# Copy_of_-5V_Buck_and_Power_Jack.net
KiCad netlist of a schematic drawn in Altium Designer
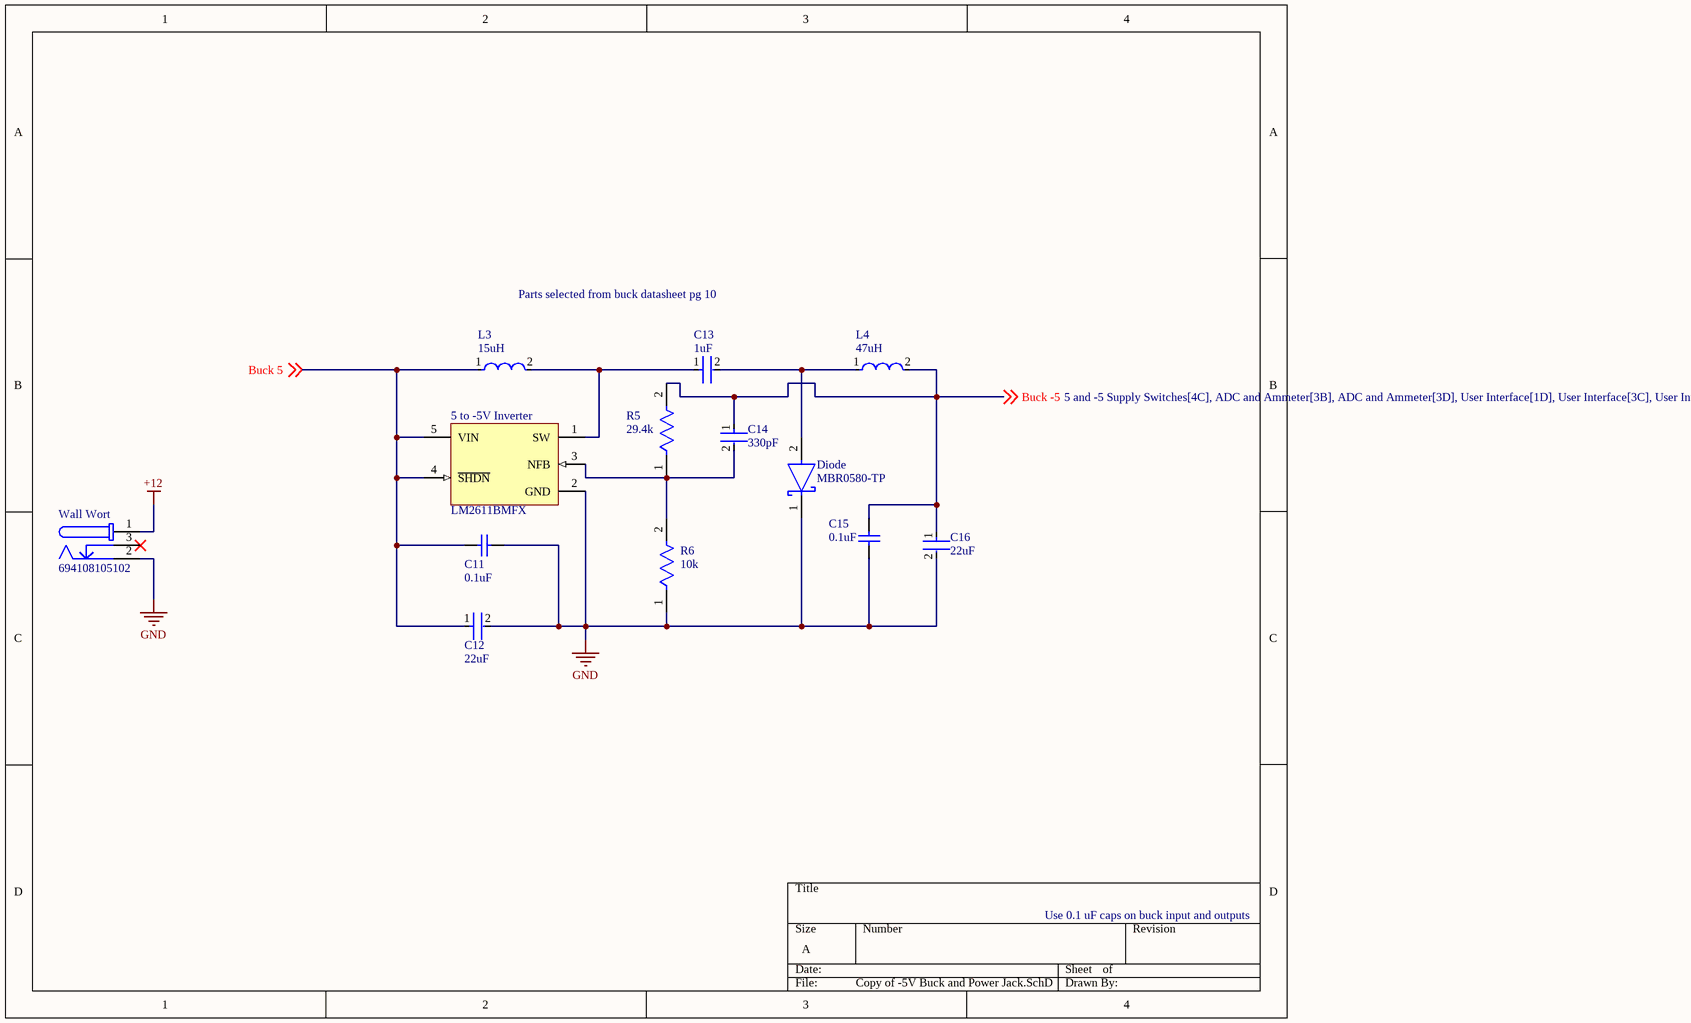
[diagram p0: Copy of -5V Buck and Power Jack.SchDoc]

(export (version "E")
  (design (tool "Eeschema 10.0.6"))
  (components
    (comp (ref "5 to -5V Inverter")
      (value "LM2611BMFX")
      (footprint "MF05A_N")
      (description "1.4MHz Cuk Converter, 5-pin SOT-23")
      (fields (field (name "MANUFACTURER") "National Semiconductor"))
      (libsource (lib "Altium Content Vault") (part "PM-DCDC-LM2611"))
    )
    (comp (ref "C11")
      (value "0.1uF")
      (footprint "CAPC2013X94X50LL20T25")
      (fields
        (field (name "PART NUMBER") "08055C104JAT4A")
        (field (name "MANUFACTURER") "AVX Interconnect / Elco")
      )
      (libsource (lib "Altium Content Vault") (part "CAP"))
    )
    (comp (ref "C12")
      (value "22uF")
      (footprint "FP-CL21-IPC_C")
      (description "CL21 Series 0805 22uF 25V ±20% Tolerance X5R Multilayer Ceramic Chip Capacitor")
      (libsource (lib "Altium Content Vault") (part "b4654b650e69147ec39a6b967a45e02"))
    )
    (comp (ref "C13")
      (value "1uF")
      (footprint "FP-CL10-IPC_B")
      (description "Cap Ceramic 1uF 25V X5R ±10% Pad SMD 0603 +85°C T/R")
      (fields (field (name "TOLERANCE") "10%"))
      (libsource (lib "Altium Content Vault") (part "b4654b650e69147ec39a6b967a45e02"))
    )
    (comp (ref "C14")
      (value "330pF")
      (footprint "FP-C0603C-CF-MFG")
      (description "C0603 330 pF X8R 30ppm/°C 20.00% 50 V")
      (fields (field (name "TOLERANCE") "0.2") (field (name "MANUFACTURER") "KEMET"))
      (libsource (lib "Altium Content Vault") (part "b4654b650e69147ec39a6b967a45e02"))
    )
    (comp (ref "C15")
      (value "0.1uF")
      (footprint "CAPC2013X94X50LL20T25")
      (fields
        (field (name "PART NUMBER") "08055C104JAT4A")
        (field (name "MANUFACTURER") "AVX Interconnect / Elco")
      )
      (libsource (lib "Altium Content Vault") (part "CAP"))
    )
    (comp (ref "C16")
      (value "22uF")
      (footprint "FP-CL21-IPC_C")
      (description "CL21 Series 0805 22uF 25V ±20% Tolerance X5R Multilayer Ceramic Chip Capacitor")
      (libsource (lib "Altium Content Vault") (part "b4654b650e69147ec39a6b967a45e02"))
    )
    (comp (ref "Diode")
      (value "MBR0580-TP")
      (footprint "FP-SOD-123-IPC_C")
      (description "DIODE SCHOTTKY 80V 500MA SOD123")
      (libsource (lib "Altium Content Vault") (part "1d6ec82d83fb6aee721767c19dac4b9"))
    )
    (comp (ref "L3")
      (value "15uH")
      (footprint "FP-SRR1260-MFG")
      (description "FIXED IND 15UH 5A 27 MOHM SMD")
      (fields (field (name "TOLERANCE") "20%"))
      (libsource (lib "Altium Content Vault") (part "725321dda6339637d4d059423bc1c3c"))
    )
    (comp (ref "L4")
      (value "47uH")
      (footprint "FP-SRP1265A-MFG")
      (description "FIXED IND 47UH 6.5A 90 MOHM SMD")
      (fields (field (name "TOLERANCE") "20%"))
      (libsource (lib "Altium Content Vault") (part "725321dda6339637d4d059423bc1c3c"))
    )
    (comp (ref "R5")
      (value "29.4k")
      (footprint "FP-AC0603-MFG")
      (description "RES 29.4KΩ 1.00% 0.1W 0603")
      (fields (field (name "TOLERANCE") "1%"))
      (libsource (lib "Altium Content Vault") (part "1029c3af85768c4190bb7ad29bc67b5"))
    )
    (comp (ref "R6")
      (value "10k")
      (footprint "FP-RK73H1J-IPC_B")
      (description "10kΩ ±1% 0.1W Chip Resistor 0603 Thick Film AEC-Q200 Qualified")
      (fields (field (name "TOLERANCE") "1%"))
      (libsource (lib "Altium Content Vault") (part "1029c3af85768c4190bb7ad29bc67b5"))
    )
    (comp (ref "Wall Wort")
      (value "694108105102")
      (footprint "694108105102")
      (libsource (lib "Altium Content Vault") (part "DC Power Jack"))
    )
  )
  (nets
    (net (code "1") (name "+12") (class "Default")
      (node (ref "Wall Wort") (pin "1") (pinfunction "1_1") (pintype "passive"))
    )
    (net (code "2") (name "Buck -5") (class "Default")
      (node (ref "C14") (pin "1") (pinfunction "1_1") (pintype "passive"))
      (node (ref "C15") (pin "2") (pinfunction "2_2") (pintype "passive"))
      (node (ref "C16") (pin "1") (pinfunction "1_1") (pintype "passive"))
      (node (ref "L4") (pin "2") (pinfunction "2_2") (pintype "passive"))
      (node (ref "R5") (pin "2") (pinfunction "2_2") (pintype "passive"))
    )
    (net (code "3") (name "Buck 5") (class "Default")
      (node (ref "5 to -5V Inverter") (pin "4") (pinfunction "~{SHDN}_4") (pintype "input"))
      (node (ref "5 to -5V Inverter") (pin "5") (pinfunction "VIN_5") (pintype "power_in"))
      (node (ref "C11") (pin "1") (pinfunction "1_1") (pintype "passive"))
      (node (ref "C12") (pin "1") (pinfunction "1_1") (pintype "passive"))
      (node (ref "L3") (pin "1") (pinfunction "1_1") (pintype "passive"))
    )
    (net (code "4") (name "GND") (class "Default")
      (node (ref "5 to -5V Inverter") (pin "2") (pinfunction "GND_2") (pintype "power_in"))
      (node (ref "C11") (pin "2") (pinfunction "2_2") (pintype "passive"))
      (node (ref "C12") (pin "2") (pinfunction "2_2") (pintype "passive"))
      (node (ref "C15") (pin "1") (pinfunction "1_1") (pintype "passive"))
      (node (ref "C16") (pin "2") (pinfunction "2_2") (pintype "passive"))
      (node (ref "Diode") (pin "1") (pinfunction "C_1") (pintype "passive"))
      (node (ref "R6") (pin "1") (pinfunction "1_1") (pintype "passive"))
      (node (ref "Wall Wort") (pin "2") (pinfunction "2_2") (pintype "passive"))
    )
    (net (code "5") (name "Net-(5 to -5V Inverter-NFB)") (class "Default")
      (node (ref "5 to -5V Inverter") (pin "3") (pinfunction "NFB_3") (pintype "input"))
      (node (ref "C14") (pin "2") (pinfunction "2_2") (pintype "passive"))
      (node (ref "R5") (pin "1") (pinfunction "1_1") (pintype "passive"))
      (node (ref "R6") (pin "2") (pinfunction "2_2") (pintype "passive"))
    )
    (net (code "6") (name "Net-(5 to -5V Inverter-SW)") (class "Default")
      (node (ref "5 to -5V Inverter") (pin "1") (pinfunction "SW_1") (pintype "power_in"))
      (node (ref "C13") (pin "1") (pinfunction "1_1") (pintype "passive"))
      (node (ref "L3") (pin "2") (pinfunction "2_2") (pintype "passive"))
    )
    (net (code "7") (name "Net-(Diode-A)") (class "Default")
      (node (ref "C13") (pin "2") (pinfunction "2_2") (pintype "passive"))
      (node (ref "Diode") (pin "2") (pinfunction "A_2") (pintype "passive"))
      (node (ref "L4") (pin "1") (pinfunction "1_1") (pintype "passive"))
    )
    (net (code "8") (name "unconnected-(Wall Wort-Pad3)") (class "Default")
      (node (ref "Wall Wort") (pin "3") (pinfunction "3_3") (pintype "passive+no_connect"))
    )
  )
)
